# Eagle_schematic.net
KiCad netlist of a schematic drawn in EAGLE
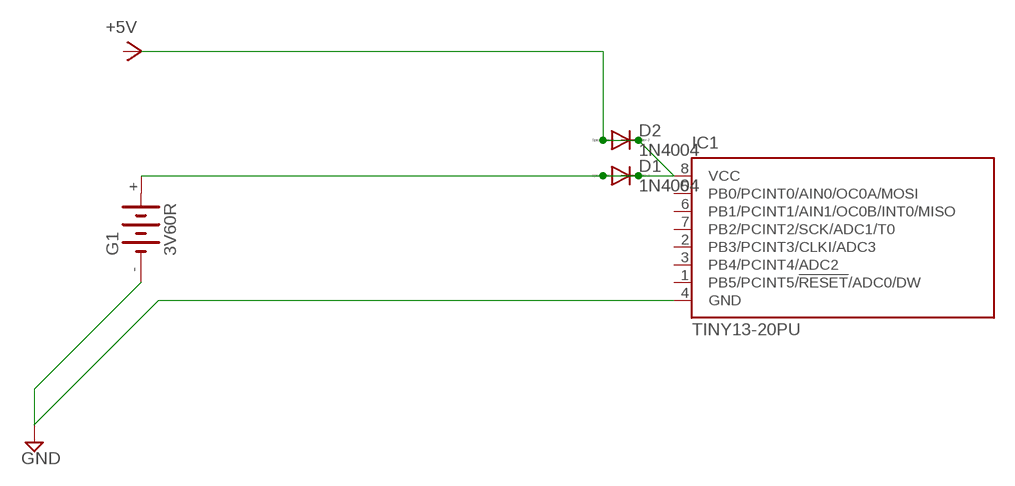
[diagram p0: schematic, sheet 1]

(export (version "E")
  (design (tool "Eeschema 10.0.6"))
  (components
    (comp (ref "D1")
      (value "1N4004")
      (footprint "eagle-import:DO41-10")
      (libsource (lib "eagle-import") (part "1N4004"))
    )
    (comp (ref "D2")
      (value "1N4004")
      (footprint "eagle-import:DO41-10")
      (libsource (lib "eagle-import") (part "1N4004"))
    )
    (comp (ref "G1")
      (value "3V60R")
      (footprint "eagle-import:3V60R")
      (libsource (lib "eagle-import") (part "3V60R"))
    )
    (comp (ref "IC1")
      (value "TINY13-20PU")
      (footprint "eagle-import:DIL08")
      (fields (field (name "MPN") "ATTINY13-20PU"))
      (libsource (lib "eagle-import") (part "TINY13PU-20"))
    )
  )
  (nets
    (net (code "2") (name "GND") (class "Default")
      (node (ref "G1") (pin "-") (pinfunction "-_-") (pintype "passive"))
      (node (ref "IC1") (pin "4") (pinfunction "GND_4") (pintype "power_in"))
    )
    (net (code "3") (name "Net-(IC1-VCC)") (class "Default")
      (node (ref "D1") (pin "A") (pinfunction "A_A") (pintype "passive"))
      (node (ref "D1") (pin "C") (pinfunction "C_C") (pintype "passive"))
      (node (ref "D2") (pin "A") (pinfunction "A_A") (pintype "passive"))
      (node (ref "D2") (pin "C") (pinfunction "C_C") (pintype "passive"))
      (node (ref "G1") (pin "+") (pinfunction "+_+") (pintype "passive"))
      (node (ref "IC1") (pin "8") (pinfunction "VCC_8") (pintype "power_in"))
    )
    (net (code "4") (name "unconnected-(G1-+-Pad+@1)") (class "Default")
      (node (ref "G1") (pin "+@1") (pinfunction "+_+@1") (pintype "passive"))
    )
    (net (code "5") (name "unconnected-(IC1-PB0{slash}PCINT0{slash}AIN0{slash}OC0A{slash}MOSI-Pad5)") (class "Default")
      (node (ref "IC1") (pin "5") (pinfunction "PB0/PCINT0/AIN0/OC0A/MOSI_5") (pintype "bidirectional"))
    )
    (net (code "6") (name "unconnected-(IC1-PB1{slash}PCINT1{slash}AIN1{slash}OC0B{slash}INT0{slash}MISO-Pad6)") (class "Default")
      (node (ref "IC1") (pin "6") (pinfunction "PB1/PCINT1/AIN1/OC0B/INT0/MISO_6") (pintype "bidirectional"))
    )
    (net (code "7") (name "unconnected-(IC1-PB2{slash}PCINT2{slash}SCK{slash}ADC1{slash}T0-Pad7)") (class "Default")
      (node (ref "IC1") (pin "7") (pinfunction "PB2/PCINT2/SCK/ADC1/T0_7") (pintype "bidirectional"))
    )
    (net (code "8") (name "unconnected-(IC1-PB3{slash}PCINT3{slash}CLKI{slash}ADC3-Pad2)") (class "Default")
      (node (ref "IC1") (pin "2") (pinfunction "PB3/PCINT3/CLKI/ADC3_2") (pintype "bidirectional"))
    )
    (net (code "9") (name "unconnected-(IC1-PB4{slash}PCINT4{slash}ADC2-Pad3)") (class "Default")
      (node (ref "IC1") (pin "3") (pinfunction "PB4/PCINT4/ADC2_3") (pintype "bidirectional"))
    )
    (net (code "10") (name "unconnected-(IC1-PB5{slash}PCINT5{slash}~{RESET}{slash}ADC0{slash}DW-Pad1)") (class "Default")
      (node (ref "IC1") (pin "1") (pinfunction "PB5/PCINT5/~{RESET}/ADC0/DW_1") (pintype "bidirectional"))
    )
  )
)
